# THAT-breakouts.net
KiCad netlist of a schematic drawn in EAGLE
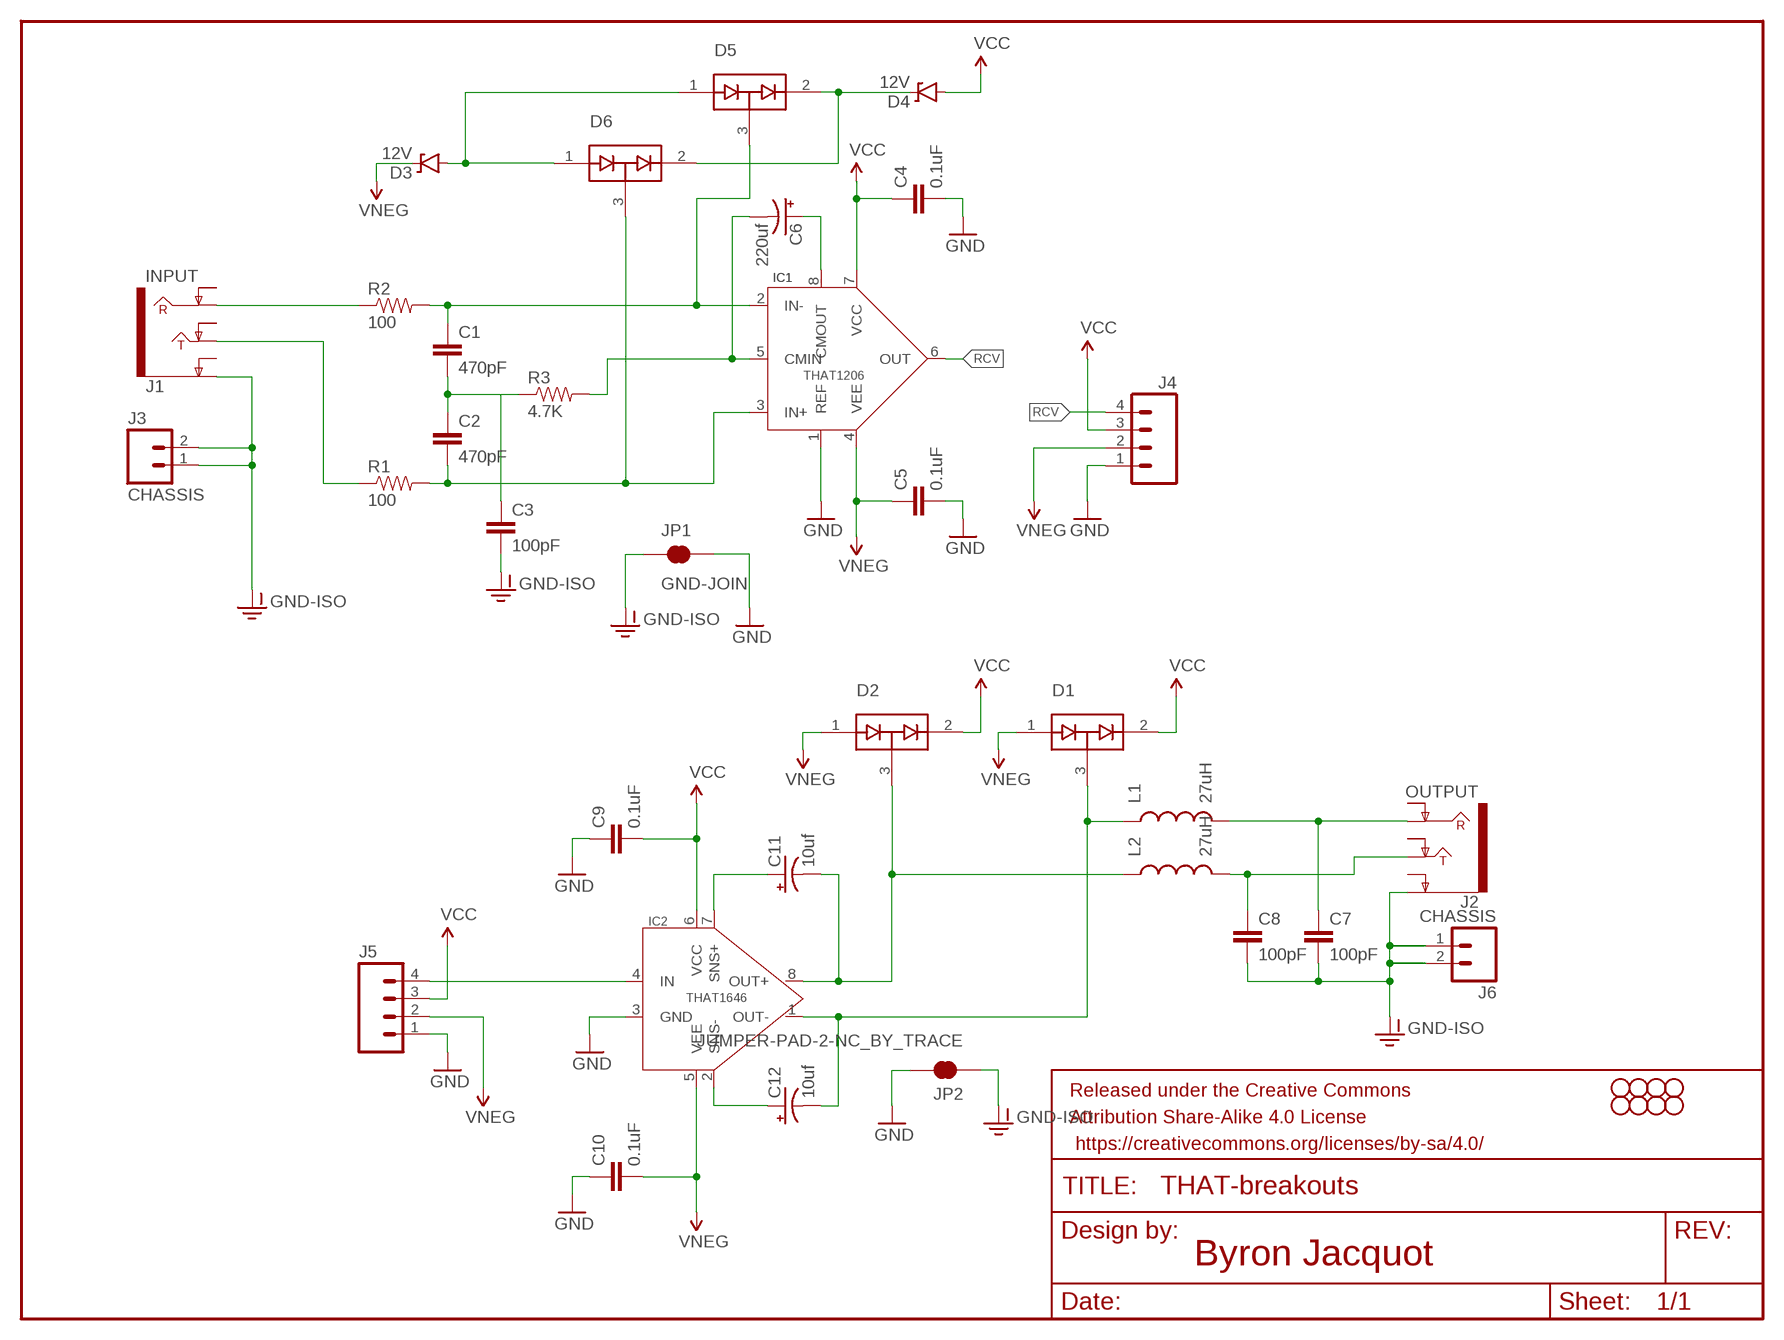
[diagram p0: schematic, sheet 1]

(export (version "E")
  (design (tool "Eeschema 10.0.6"))
  (components
    (comp (ref "C1")
      (value "470pF")
      (footprint "eagle-import:0603-CAP")
      (libsource (lib "eagle-import") (part "470PF-50V-5%(0603)SMD"))
    )
    (comp (ref "C2")
      (value "470pF")
      (footprint "eagle-import:0603-CAP")
      (libsource (lib "eagle-import") (part "470PF-50V-5%(0603)SMD"))
    )
    (comp (ref "C3")
      (value "100pF")
      (footprint "eagle-import:0603-CAP")
      (libsource (lib "eagle-import") (part "100PF-50V-5%(0603)"))
    )
    (comp (ref "C4")
      (value "0.1uF")
      (footprint "eagle-import:0603-CAP")
      (libsource (lib "eagle-import") (part "0.1UF-25V-5%(0603)"))
    )
    (comp (ref "C5")
      (value "0.1uF")
      (footprint "eagle-import:0603-CAP")
      (libsource (lib "eagle-import") (part "0.1UF-25V-5%(0603)"))
    )
    (comp (ref "C6")
      (value "220uf")
      (footprint "eagle-import:PANASONIC_D")
      (libsource (lib "eagle-import") (part "PANA-EEE-FKOJ221P"))
    )
    (comp (ref "C7")
      (value "100pF")
      (footprint "eagle-import:0603-CAP")
      (libsource (lib "eagle-import") (part "100PF-50V-5%(0603)"))
    )
    (comp (ref "C8")
      (value "100pF")
      (footprint "eagle-import:0603-CAP")
      (libsource (lib "eagle-import") (part "100PF-50V-5%(0603)"))
    )
    (comp (ref "C9")
      (value "0.1uF")
      (footprint "eagle-import:0603-CAP")
      (libsource (lib "eagle-import") (part "0.1UF-25V-5%(0603)"))
    )
    (comp (ref "C10")
      (value "0.1uF")
      (footprint "eagle-import:0603-CAP")
      (libsource (lib "eagle-import") (part "0.1UF-25V-5%(0603)"))
    )
    (comp (ref "C11")
      (value "10uf")
      (footprint "eagle-import:PANASONIC_D")
      (libsource (lib "eagle-import") (part "PANA-EEE-1EA100NP"))
    )
    (comp (ref "C12")
      (value "10uf")
      (footprint "eagle-import:PANASONIC_D")
      (libsource (lib "eagle-import") (part "PANA-EEE-1EA100NP"))
    )
    (comp (ref "D1")
      (value "BAV99")
      (footprint "eagle-import:SOT23-3")
      (libsource (lib "eagle-import") (part "BAV99"))
    )
    (comp (ref "D2")
      (value "BAV99")
      (footprint "eagle-import:SOT23-3")
      (libsource (lib "eagle-import") (part "BAV99"))
    )
    (comp (ref "D3")
      (value "12V")
      (footprint "eagle-import:SOD-323")
      (fields (field (name "MFR") "ON Semi"))
      (libsource (lib "eagle-import") (part "12V-ZENER-DIODE"))
    )
    (comp (ref "D4")
      (value "12V")
      (footprint "eagle-import:SOD-323")
      (fields (field (name "MFR") "ON Semi"))
      (libsource (lib "eagle-import") (part "12V-ZENER-DIODE"))
    )
    (comp (ref "D5")
      (value "BAV99")
      (footprint "eagle-import:SOT23-3")
      (libsource (lib "eagle-import") (part "BAV99"))
    )
    (comp (ref "D6")
      (value "BAV99")
      (footprint "eagle-import:SOT23-3")
      (libsource (lib "eagle-import") (part "BAV99"))
    )
    (comp (ref "FRAME1")
      (value "FRAME-LETTER")
      (footprint "eagle-import:CREATIVE_COMMONS")
      (libsource (lib "eagle-import") (part "FRAME-LETTER"))
    )
    (comp (ref "H1")
      (value "STAND-OFF")
      (footprint "eagle-import:STAND-OFF")
      (libsource (lib "eagle-import") (part "STAND-OFF"))
    )
    (comp (ref "H2")
      (value "STAND-OFF")
      (footprint "eagle-import:STAND-OFF")
      (libsource (lib "eagle-import") (part "STAND-OFF"))
    )
    (comp (ref "H3")
      (value "STAND-OFF")
      (footprint "eagle-import:STAND-OFF")
      (libsource (lib "eagle-import") (part "STAND-OFF"))
    )
    (comp (ref "H4")
      (value "STAND-OFF")
      (footprint "eagle-import:STAND-OFF")
      (libsource (lib "eagle-import") (part "STAND-OFF"))
    )
    (comp (ref "H5")
      (value "STAND-OFF")
      (footprint "eagle-import:STAND-OFF")
      (libsource (lib "eagle-import") (part "STAND-OFF"))
    )
    (comp (ref "H6")
      (value "STAND-OFF")
      (footprint "eagle-import:STAND-OFF")
      (libsource (lib "eagle-import") (part "STAND-OFF"))
    )
    (comp (ref "H7")
      (value "STAND-OFF")
      (footprint "eagle-import:STAND-OFF")
      (libsource (lib "eagle-import") (part "STAND-OFF"))
    )
    (comp (ref "H8")
      (value "STAND-OFF")
      (footprint "eagle-import:STAND-OFF")
      (libsource (lib "eagle-import") (part "STAND-OFF"))
    )
    (comp (ref "IC1")
      (value "THAT1206")
      (footprint "eagle-import:SO08")
      (libsource (lib "eagle-import") (part "THAT1206"))
    )
    (comp (ref "IC2")
      (value "THAT1646")
      (footprint "eagle-import:SO08")
      (libsource (lib "eagle-import") (part "THAT1646"))
    )
    (comp (ref "J1")
      (value "INPUT")
      (footprint "eagle-import:AUDIO-JACK-.25-INCH-HORIZ-PTH")
      (libsource (lib "eagle-import") (part "AUDIO-JACK4-.25-HORIZ-TRS"))
    )
    (comp (ref "J2")
      (value "OUTPUT")
      (footprint "eagle-import:AUDIO-JACK-.25-INCH-HORIZ-PTH")
      (libsource (lib "eagle-import") (part "AUDIO-JACK4-.25-HORIZ-TRS"))
    )
    (comp (ref "J3")
      (value "CHASSIS")
      (footprint "eagle-import:1X02_NO_SILK")
      (libsource (lib "eagle-import") (part "M021X02_NO_SILK"))
    )
    (comp (ref "J4")
      (value "M04NO_SILK_ALL_ROUND")
      (footprint "eagle-import:1X04_NO_SILK_ALL_ROUND")
      (libsource (lib "eagle-import") (part "M04NO_SILK_ALL_ROUND"))
    )
    (comp (ref "J5")
      (value "M04NO_SILK_ALL_ROUND")
      (footprint "eagle-import:1X04_NO_SILK_ALL_ROUND")
      (libsource (lib "eagle-import") (part "M04NO_SILK_ALL_ROUND"))
    )
    (comp (ref "J6")
      (value "CHASSIS")
      (footprint "eagle-import:1X02_NO_SILK")
      (libsource (lib "eagle-import") (part "M021X02_NO_SILK"))
    )
    (comp (ref "JP1")
      (value "GND-JOIN")
      (footprint "eagle-import:PAD-JUMPER-2-NC_BY_TRACE_YES_SILK")
      (libsource (lib "eagle-import") (part "JUMPER-PAD-2-NC_BY_TRACE"))
    )
    (comp (ref "JP2")
      (value "JUMPER-PAD-2-NC_BY_TRACE")
      (footprint "eagle-import:PAD-JUMPER-2-NC_BY_TRACE_YES_SILK")
      (libsource (lib "eagle-import") (part "JUMPER-PAD-2-NC_BY_TRACE"))
    )
    (comp (ref "L1")
      (value "27uH")
      (footprint "eagle-import:0603")
      (libsource (lib "eagle-import") (part "INDUCTOR0603"))
    )
    (comp (ref "L2")
      (value "27uH")
      (footprint "eagle-import:0603")
      (libsource (lib "eagle-import") (part "INDUCTOR0603"))
    )
    (comp (ref "R1")
      (value "100")
      (footprint "eagle-import:0603-RES")
      (libsource (lib "eagle-import") (part "100OHM-1/10W-1%(0603)"))
    )
    (comp (ref "R2")
      (value "100")
      (footprint "eagle-import:0603-RES")
      (libsource (lib "eagle-import") (part "100OHM-1/10W-1%(0603)"))
    )
    (comp (ref "R3")
      (value "4.7K")
      (footprint "eagle-import:0603-RES")
      (libsource (lib "eagle-import") (part "4.7KOHM-1/10W-1%(0603)"))
    )
  )
  (nets
    (net (code "1") (name "GND") (class "Default")
      (node (ref "C10") (pin "1") (pinfunction "1_1") (pintype "passive"))
      (node (ref "C4") (pin "2") (pinfunction "2_2") (pintype "passive"))
      (node (ref "C5") (pin "2") (pinfunction "2_2") (pintype "passive"))
      (node (ref "C9") (pin "1") (pinfunction "1_1") (pintype "passive"))
      (node (ref "IC1") (pin "1") (pinfunction "REF_1") (pintype "bidirectional"))
      (node (ref "IC2") (pin "3") (pinfunction "GND_3") (pintype "bidirectional"))
      (node (ref "J4") (pin "1") (pinfunction "1_1") (pintype "passive"))
      (node (ref "J5") (pin "1") (pinfunction "1_1") (pintype "passive"))
      (node (ref "JP1") (pin "2") (pinfunction "2_2") (pintype "passive"))
      (node (ref "JP2") (pin "2") (pinfunction "2_2") (pintype "passive"))
    )
    (net (code "2") (name "GND-ISO") (class "Default")
      (node (ref "C3") (pin "2") (pinfunction "2_2") (pintype "passive"))
      (node (ref "C7") (pin "2") (pinfunction "2_2") (pintype "passive"))
      (node (ref "C8") (pin "2") (pinfunction "2_2") (pintype "passive"))
      (node (ref "J1") (pin "SLEEVE") (pinfunction "EARTH_SLEEVE") (pintype "bidirectional"))
      (node (ref "J2") (pin "SLEEVE") (pinfunction "EARTH_SLEEVE") (pintype "bidirectional"))
      (node (ref "J3") (pin "1") (pinfunction "1_1") (pintype "passive"))
      (node (ref "J3") (pin "2") (pinfunction "2_2") (pintype "passive"))
      (node (ref "J6") (pin "1") (pinfunction "1_1") (pintype "passive"))
      (node (ref "J6") (pin "2") (pinfunction "2_2") (pintype "passive"))
      (node (ref "JP1") (pin "1") (pinfunction "1_1") (pintype "passive"))
      (node (ref "JP2") (pin "1") (pinfunction "1_1") (pintype "passive"))
    )
    (net (code "3") (name "Net-(C1-Pad2)") (class "Default")
      (node (ref "C1") (pin "2") (pinfunction "2_2") (pintype "passive"))
      (node (ref "C2") (pin "1") (pinfunction "1_1") (pintype "passive"))
      (node (ref "C3") (pin "1") (pinfunction "1_1") (pintype "passive"))
      (node (ref "R3") (pin "1") (pinfunction "1_1") (pintype "passive"))
    )
    (net (code "4") (name "Net-(C7-Pad1)") (class "Default")
      (node (ref "C7") (pin "1") (pinfunction "1_1") (pintype "passive"))
      (node (ref "J2") (pin "RING") (pinfunction "RING_RING") (pintype "bidirectional"))
      (node (ref "L1") (pin "2") (pinfunction "2_2") (pintype "passive"))
    )
    (net (code "5") (name "Net-(C8-Pad1)") (class "Default")
      (node (ref "C8") (pin "1") (pinfunction "1_1") (pintype "passive"))
      (node (ref "J2") (pin "TIP") (pinfunction "TIP_TIP") (pintype "bidirectional"))
      (node (ref "L2") (pin "2") (pinfunction "2_2") (pintype "passive"))
    )
    (net (code "6") (name "Net-(D1-COM)") (class "Default")
      (node (ref "C12") (pin "-") (pinfunction "-_-") (pintype "passive"))
      (node (ref "D1") (pin "3") (pinfunction "COM_3") (pintype "bidirectional"))
      (node (ref "IC2") (pin "1") (pinfunction "OUT-_1") (pintype "bidirectional"))
      (node (ref "L1") (pin "1") (pinfunction "1_1") (pintype "passive"))
    )
    (net (code "7") (name "Net-(D2-COM)") (class "Default")
      (node (ref "C11") (pin "-") (pinfunction "-_-") (pintype "passive"))
      (node (ref "D2") (pin "3") (pinfunction "COM_3") (pintype "bidirectional"))
      (node (ref "IC2") (pin "8") (pinfunction "OUT+_8") (pintype "bidirectional"))
      (node (ref "L2") (pin "1") (pinfunction "1_1") (pintype "passive"))
    )
    (net (code "8") (name "Net-(D5-A1)") (class "Default")
      (node (ref "D3") (pin "A") (pinfunction "A_A") (pintype "passive"))
      (node (ref "D5") (pin "1") (pinfunction "A1_1") (pintype "bidirectional"))
      (node (ref "D6") (pin "1") (pinfunction "A1_1") (pintype "bidirectional"))
    )
    (net (code "9") (name "Net-(D5-C2)") (class "Default")
      (node (ref "D4") (pin "C") (pinfunction "C_C") (pintype "passive"))
      (node (ref "D5") (pin "2") (pinfunction "C2_2") (pintype "bidirectional"))
      (node (ref "D6") (pin "2") (pinfunction "C2_2") (pintype "bidirectional"))
    )
    (net (code "10") (name "Net-(D5-COM)") (class "Default")
      (node (ref "C1") (pin "1") (pinfunction "1_1") (pintype "passive"))
      (node (ref "D5") (pin "3") (pinfunction "COM_3") (pintype "bidirectional"))
      (node (ref "IC1") (pin "2") (pinfunction "IN-_2") (pintype "bidirectional"))
      (node (ref "R2") (pin "2") (pinfunction "2_2") (pintype "passive"))
    )
    (net (code "11") (name "Net-(D6-COM)") (class "Default")
      (node (ref "C2") (pin "2") (pinfunction "2_2") (pintype "passive"))
      (node (ref "D6") (pin "3") (pinfunction "COM_3") (pintype "bidirectional"))
      (node (ref "IC1") (pin "3") (pinfunction "IN+_3") (pintype "bidirectional"))
      (node (ref "R1") (pin "2") (pinfunction "2_2") (pintype "passive"))
    )
    (net (code "12") (name "Net-(IC1-CMIN)") (class "Default")
      (node (ref "C6") (pin "-") (pinfunction "-_-") (pintype "passive"))
      (node (ref "IC1") (pin "5") (pinfunction "CMIN_5") (pintype "bidirectional"))
      (node (ref "R3") (pin "2") (pinfunction "2_2") (pintype "passive"))
    )
    (net (code "13") (name "Net-(IC1-CMOUT)") (class "Default")
      (node (ref "C6") (pin "+") (pinfunction "+_+") (pintype "passive"))
      (node (ref "IC1") (pin "8") (pinfunction "CMOUT_8") (pintype "bidirectional"))
    )
    (net (code "14") (name "Net-(IC2-IN)") (class "Default")
      (node (ref "IC2") (pin "4") (pinfunction "IN_4") (pintype "bidirectional"))
      (node (ref "J5") (pin "4") (pinfunction "4_4") (pintype "passive"))
    )
    (net (code "15") (name "Net-(IC2-SNS+)") (class "Default")
      (node (ref "C11") (pin "+") (pinfunction "+_+") (pintype "passive"))
      (node (ref "IC2") (pin "7") (pinfunction "SNS+_7") (pintype "bidirectional"))
    )
    (net (code "16") (name "Net-(IC2-SNS-)") (class "Default")
      (node (ref "C12") (pin "+") (pinfunction "+_+") (pintype "passive"))
      (node (ref "IC2") (pin "2") (pinfunction "SNS-_2") (pintype "bidirectional"))
    )
    (net (code "17") (name "Net-(J1-PadRING)") (class "Default")
      (node (ref "J1") (pin "RING") (pinfunction "RING_RING") (pintype "bidirectional"))
      (node (ref "R2") (pin "1") (pinfunction "1_1") (pintype "passive"))
    )
    (net (code "18") (name "Net-(J1-PadTIP)") (class "Default")
      (node (ref "J1") (pin "TIP") (pinfunction "TIP_TIP") (pintype "bidirectional"))
      (node (ref "R1") (pin "1") (pinfunction "1_1") (pintype "passive"))
    )
    (net (code "19") (name "RCV") (class "Default")
      (node (ref "IC1") (pin "6") (pinfunction "OUT_6") (pintype "bidirectional"))
      (node (ref "J4") (pin "4") (pinfunction "4_4") (pintype "passive"))
    )
    (net (code "20") (name "VCC") (class "Default")
      (node (ref "C4") (pin "1") (pinfunction "1_1") (pintype "passive"))
      (node (ref "C9") (pin "2") (pinfunction "2_2") (pintype "passive"))
      (node (ref "D1") (pin "2") (pinfunction "C2_2") (pintype "bidirectional"))
      (node (ref "D2") (pin "2") (pinfunction "C2_2") (pintype "bidirectional"))
      (node (ref "D4") (pin "A") (pinfunction "A_A") (pintype "passive"))
      (node (ref "IC1") (pin "7") (pinfunction "VCC_7") (pintype "bidirectional"))
      (node (ref "IC2") (pin "6") (pinfunction "VCC_6") (pintype "bidirectional"))
      (node (ref "J4") (pin "3") (pinfunction "3_3") (pintype "passive"))
      (node (ref "J5") (pin "3") (pinfunction "3_3") (pintype "passive"))
    )
    (net (code "21") (name "VNEG") (class "Default")
      (node (ref "C10") (pin "2") (pinfunction "2_2") (pintype "passive"))
      (node (ref "C5") (pin "1") (pinfunction "1_1") (pintype "passive"))
      (node (ref "D1") (pin "1") (pinfunction "A1_1") (pintype "bidirectional"))
      (node (ref "D2") (pin "1") (pinfunction "A1_1") (pintype "bidirectional"))
      (node (ref "D3") (pin "C") (pinfunction "C_C") (pintype "passive"))
      (node (ref "IC1") (pin "4") (pinfunction "VEE_4") (pintype "bidirectional"))
      (node (ref "IC2") (pin "5") (pinfunction "VEE_5") (pintype "bidirectional"))
      (node (ref "J4") (pin "2") (pinfunction "2_2") (pintype "passive"))
      (node (ref "J5") (pin "2") (pinfunction "2_2") (pintype "passive"))
    )
    (net (code "22") (name "unconnected-(J1-EARTH-NORM-PadSLEEVE-NORM)") (class "Default")
      (node (ref "J1") (pin "SLEEVE-NORM") (pinfunction "EARTH-NORM_SLEEVE-NORM") (pintype "bidirectional"))
    )
    (net (code "23") (name "unconnected-(J1-PadRING-NORM)") (class "Default")
      (node (ref "J1") (pin "RING-NORM") (pinfunction "RING-NORM_RING-NORM") (pintype "bidirectional"))
    )
    (net (code "24") (name "unconnected-(J1-PadTIP-NORM)") (class "Default")
      (node (ref "J1") (pin "TIP-NORM") (pinfunction "TIP-NORM_TIP-NORM") (pintype "bidirectional"))
    )
    (net (code "25") (name "unconnected-(J2-EARTH-NORM-PadSLEEVE-NORM)") (class "Default")
      (node (ref "J2") (pin "SLEEVE-NORM") (pinfunction "EARTH-NORM_SLEEVE-NORM") (pintype "bidirectional"))
    )
    (net (code "26") (name "unconnected-(J2-PadRING-NORM)") (class "Default")
      (node (ref "J2") (pin "RING-NORM") (pinfunction "RING-NORM_RING-NORM") (pintype "bidirectional"))
    )
    (net (code "27") (name "unconnected-(J2-PadTIP-NORM)") (class "Default")
      (node (ref "J2") (pin "TIP-NORM") (pinfunction "TIP-NORM_TIP-NORM") (pintype "bidirectional"))
    )
  )
)
